# untitled.net
KiCad netlist of a schematic drawn in EAGLE
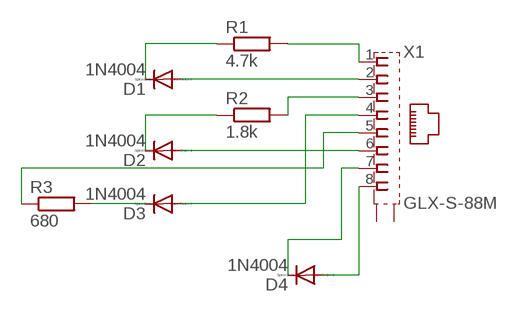
[diagram p0: schematic, sheet 1]

(export (version "E")
  (design (tool "Eeschema 10.0.6"))
  (components
    (comp (ref "D1")
      (value "1N4004")
      (footprint "eagle-import:DO41-10")
      (fields (field (name "MF") "VISHAY") (field (name "MPN") "1N4004-E3/54"))
      (libsource (lib "eagle-import") (part "1N4004"))
    )
    (comp (ref "D2")
      (value "1N4004")
      (footprint "eagle-import:DO41-10")
      (fields (field (name "MF") "VISHAY") (field (name "MPN") "1N4004-E3/54"))
      (libsource (lib "eagle-import") (part "1N4004"))
    )
    (comp (ref "D3")
      (value "1N4004")
      (footprint "eagle-import:DO41-10")
      (fields (field (name "MF") "VISHAY") (field (name "MPN") "1N4004-E3/54"))
      (libsource (lib "eagle-import") (part "1N4004"))
    )
    (comp (ref "D4")
      (value "1N4004")
      (footprint "eagle-import:DO41-10")
      (fields (field (name "MF") "VISHAY") (field (name "MPN") "1N4004-E3/54"))
      (libsource (lib "eagle-import") (part "1N4004"))
    )
    (comp (ref "R1")
      (value "4.7k")
      (footprint "eagle-import:0309_12")
      (fields (field (name "MF") "MULTICOMP") (field (name "MPN") "MCMF0W4FF4701A50"))
      (libsource (lib "eagle-import") (part "R-EU_0309/12"))
    )
    (comp (ref "R2")
      (value "1.8k")
      (footprint "eagle-import:0309_12")
      (fields (field (name "MF") "MULTICOMP") (field (name "MPN") "MCMF0W4FF1801A50"))
      (libsource (lib "eagle-import") (part "R-EU_0309/12"))
    )
    (comp (ref "R3")
      (value "680")
      (footprint "eagle-import:0309_12")
      (fields (field (name "MF") "MULTICOMP") (field (name "MPN") "MF50 680R"))
      (libsource (lib "eagle-import") (part "R-EU_0309/12"))
    )
    (comp (ref "X1")
      (value "GLX-S-88M")
      (footprint "eagle-import:GLX-S-88M")
      (libsource (lib "eagle-import") (part "GLX-S-88M"))
    )
  )
  (nets
    (net (code "1") (name "Net-(D1-PadA)") (class "Default")
      (node (ref "D1") (pin "A") (pinfunction "A_A") (pintype "passive"))
      (node (ref "X1") (pin "2") (pinfunction "2_2") (pintype "passive"))
    )
    (net (code "2") (name "Net-(D1-PadC)") (class "Default")
      (node (ref "D1") (pin "C") (pinfunction "C_C") (pintype "passive"))
      (node (ref "R1") (pin "1") (pinfunction "1_1") (pintype "passive"))
    )
    (net (code "3") (name "Net-(D2-PadA)") (class "Default")
      (node (ref "D2") (pin "A") (pinfunction "A_A") (pintype "passive"))
      (node (ref "X1") (pin "6") (pinfunction "6_6") (pintype "passive"))
    )
    (net (code "4") (name "Net-(D2-PadC)") (class "Default")
      (node (ref "D2") (pin "C") (pinfunction "C_C") (pintype "passive"))
      (node (ref "R2") (pin "1") (pinfunction "1_1") (pintype "passive"))
    )
    (net (code "5") (name "Net-(D3-PadA)") (class "Default")
      (node (ref "D3") (pin "A") (pinfunction "A_A") (pintype "passive"))
      (node (ref "X1") (pin "4") (pinfunction "4_4") (pintype "passive"))
    )
    (net (code "6") (name "Net-(D3-PadC)") (class "Default")
      (node (ref "D3") (pin "C") (pinfunction "C_C") (pintype "passive"))
      (node (ref "R3") (pin "2") (pinfunction "2_2") (pintype "passive"))
    )
    (net (code "7") (name "Net-(D4-PadA)") (class "Default")
      (node (ref "D4") (pin "A") (pinfunction "A_A") (pintype "passive"))
      (node (ref "X1") (pin "8") (pinfunction "8_8") (pintype "passive"))
    )
    (net (code "8") (name "Net-(D4-PadC)") (class "Default")
      (node (ref "D4") (pin "C") (pinfunction "C_C") (pintype "passive"))
      (node (ref "X1") (pin "7") (pinfunction "7_7") (pintype "passive"))
    )
    (net (code "9") (name "Net-(R1-Pad2)") (class "Default")
      (node (ref "R1") (pin "2") (pinfunction "2_2") (pintype "passive"))
      (node (ref "X1") (pin "1") (pinfunction "1_1") (pintype "passive"))
    )
    (net (code "10") (name "Net-(R2-Pad2)") (class "Default")
      (node (ref "R2") (pin "2") (pinfunction "2_2") (pintype "passive"))
      (node (ref "X1") (pin "3") (pinfunction "3_3") (pintype "passive"))
    )
    (net (code "11") (name "Net-(R3-Pad1)") (class "Default")
      (node (ref "R3") (pin "1") (pinfunction "1_1") (pintype "passive"))
      (node (ref "X1") (pin "5") (pinfunction "5_5") (pintype "passive"))
    )
    (net (code "12") (name "unconnected-(X1-PadS1)") (class "Default")
      (node (ref "X1") (pin "S1") (pinfunction "S1_S1") (pintype "passive"))
    )
    (net (code "13") (name "unconnected-(X1-PadS2)") (class "Default")
      (node (ref "X1") (pin "S2") (pinfunction "S2_S2") (pintype "passive"))
    )
  )
)
